# 2MBSIMMDIP.net
KiCad netlist of a schematic drawn in EAGLE
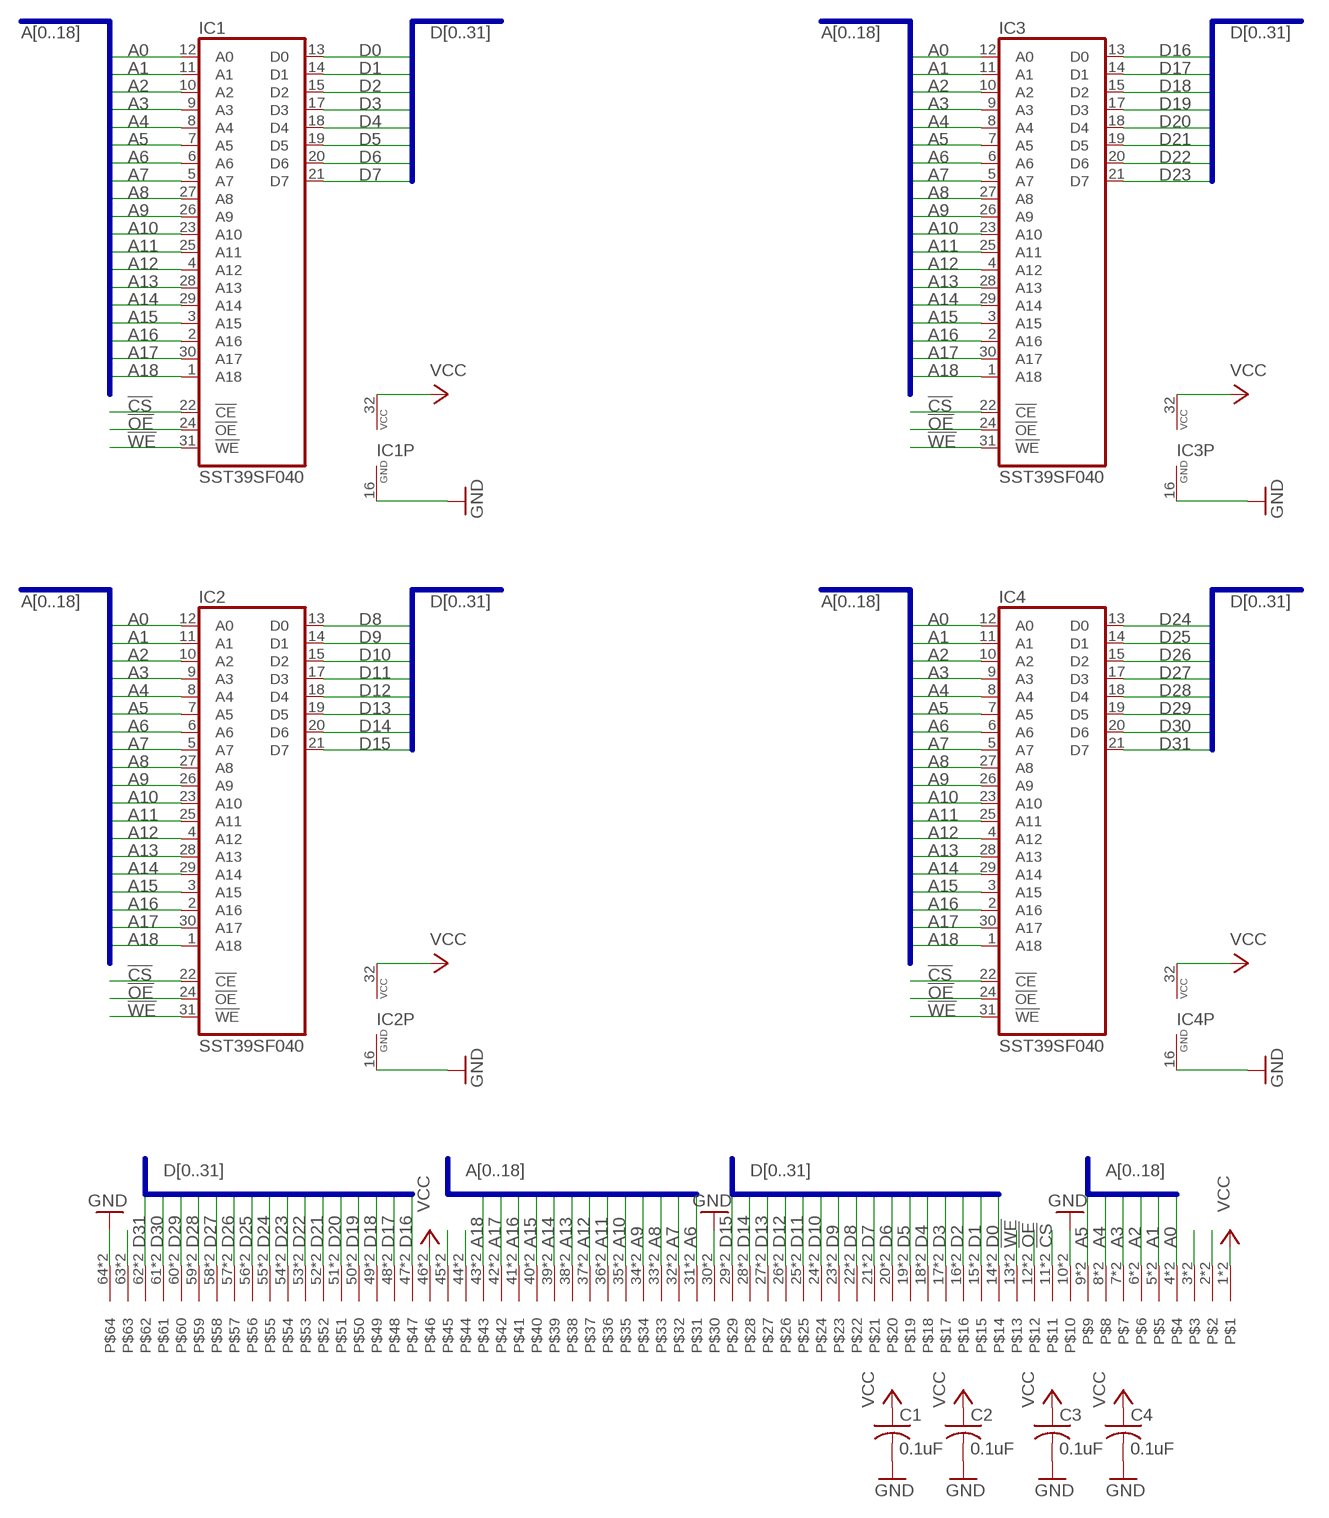
[diagram p0: schematic, sheet 1]

(export (version "E")
  (design (tool "Eeschema 10.0.6"))
  (components
    (comp (ref "C1")
      (value "0.1uF")
      (footprint "eagle-import:C1206")
      (libsource (lib "eagle-import") (part "C-USC1206"))
    )
    (comp (ref "C2")
      (value "0.1uF")
      (footprint "eagle-import:C1206")
      (libsource (lib "eagle-import") (part "C-USC1206"))
    )
    (comp (ref "C3")
      (value "0.1uF")
      (footprint "eagle-import:C1206")
      (libsource (lib "eagle-import") (part "C-USC1206"))
    )
    (comp (ref "C4")
      (value "0.1uF")
      (footprint "eagle-import:C1206")
      (libsource (lib "eagle-import") (part "C-USC1206"))
    )
    (comp (ref "CON1")
      (value "MYSIMM")
      (footprint "eagle-import:SIMM64L")
      (libsource (lib "eagle-import") (part "MYSIMM"))
    )
    (comp (ref "IC1")
      (value "SST39SF040")
      (footprint "eagle-import:DIL32-6")
      (libsource (lib "eagle-import") (part "SST39SF040"))
    )
    (comp (ref "IC2")
      (value "SST39SF040")
      (footprint "eagle-import:DIL32-6")
      (libsource (lib "eagle-import") (part "SST39SF040"))
    )
    (comp (ref "IC3")
      (value "SST39SF040")
      (footprint "eagle-import:DIL32-6")
      (libsource (lib "eagle-import") (part "SST39SF040"))
    )
    (comp (ref "IC4")
      (value "SST39SF040")
      (footprint "eagle-import:DIL32-6")
      (libsource (lib "eagle-import") (part "SST39SF040"))
    )
  )
  (nets
    (net (code "1") (name "/A0") (class "Default")
      (node (ref "CON1") (pin "4") (pinfunction "P$4_4") (pintype "bidirectional"))
      (node (ref "CON1") (pin "68") (pinfunction "P$4_68") (pintype "bidirectional"))
      (node (ref "IC1") (pin "12") (pinfunction "A0_12") (pintype "input"))
      (node (ref "IC2") (pin "12") (pinfunction "A0_12") (pintype "input"))
      (node (ref "IC3") (pin "12") (pinfunction "A0_12") (pintype "input"))
      (node (ref "IC4") (pin "12") (pinfunction "A0_12") (pintype "input"))
    )
    (net (code "2") (name "/A1") (class "Default")
      (node (ref "CON1") (pin "5") (pinfunction "P$5_5") (pintype "bidirectional"))
      (node (ref "CON1") (pin "69") (pinfunction "P$5_69") (pintype "bidirectional"))
      (node (ref "IC1") (pin "11") (pinfunction "A1_11") (pintype "input"))
      (node (ref "IC2") (pin "11") (pinfunction "A1_11") (pintype "input"))
      (node (ref "IC3") (pin "11") (pinfunction "A1_11") (pintype "input"))
      (node (ref "IC4") (pin "11") (pinfunction "A1_11") (pintype "input"))
    )
    (net (code "3") (name "/A2") (class "Default")
      (node (ref "CON1") (pin "6") (pinfunction "P$6_6") (pintype "bidirectional"))
      (node (ref "CON1") (pin "70") (pinfunction "P$6_70") (pintype "bidirectional"))
      (node (ref "IC1") (pin "10") (pinfunction "A2_10") (pintype "input"))
      (node (ref "IC2") (pin "10") (pinfunction "A2_10") (pintype "input"))
      (node (ref "IC3") (pin "10") (pinfunction "A2_10") (pintype "input"))
      (node (ref "IC4") (pin "10") (pinfunction "A2_10") (pintype "input"))
    )
    (net (code "4") (name "/A3") (class "Default")
      (node (ref "CON1") (pin "7") (pinfunction "P$7_7") (pintype "bidirectional"))
      (node (ref "CON1") (pin "71") (pinfunction "P$7_71") (pintype "bidirectional"))
      (node (ref "IC1") (pin "9") (pinfunction "A3_9") (pintype "input"))
      (node (ref "IC2") (pin "9") (pinfunction "A3_9") (pintype "input"))
      (node (ref "IC3") (pin "9") (pinfunction "A3_9") (pintype "input"))
      (node (ref "IC4") (pin "9") (pinfunction "A3_9") (pintype "input"))
    )
    (net (code "5") (name "/A4") (class "Default")
      (node (ref "CON1") (pin "72") (pinfunction "P$8_72") (pintype "bidirectional"))
      (node (ref "CON1") (pin "8") (pinfunction "P$8_8") (pintype "bidirectional"))
      (node (ref "IC1") (pin "8") (pinfunction "A4_8") (pintype "input"))
      (node (ref "IC2") (pin "8") (pinfunction "A4_8") (pintype "input"))
      (node (ref "IC3") (pin "8") (pinfunction "A4_8") (pintype "input"))
      (node (ref "IC4") (pin "8") (pinfunction "A4_8") (pintype "input"))
    )
    (net (code "6") (name "/A5") (class "Default")
      (node (ref "CON1") (pin "73") (pinfunction "P$9_73") (pintype "bidirectional"))
      (node (ref "CON1") (pin "9") (pinfunction "P$9_9") (pintype "bidirectional"))
      (node (ref "IC1") (pin "7") (pinfunction "A5_7") (pintype "input"))
      (node (ref "IC2") (pin "7") (pinfunction "A5_7") (pintype "input"))
      (node (ref "IC3") (pin "7") (pinfunction "A5_7") (pintype "input"))
      (node (ref "IC4") (pin "7") (pinfunction "A5_7") (pintype "input"))
    )
    (net (code "7") (name "/A6") (class "Default")
      (node (ref "CON1") (pin "31") (pinfunction "P$31_31") (pintype "bidirectional"))
      (node (ref "CON1") (pin "95") (pinfunction "P$31_95") (pintype "bidirectional"))
      (node (ref "IC1") (pin "6") (pinfunction "A6_6") (pintype "input"))
      (node (ref "IC2") (pin "6") (pinfunction "A6_6") (pintype "input"))
      (node (ref "IC3") (pin "6") (pinfunction "A6_6") (pintype "input"))
      (node (ref "IC4") (pin "6") (pinfunction "A6_6") (pintype "input"))
    )
    (net (code "8") (name "/A7") (class "Default")
      (node (ref "CON1") (pin "32") (pinfunction "P$32_32") (pintype "bidirectional"))
      (node (ref "CON1") (pin "96") (pinfunction "P$32_96") (pintype "bidirectional"))
      (node (ref "IC1") (pin "5") (pinfunction "A7_5") (pintype "input"))
      (node (ref "IC2") (pin "5") (pinfunction "A7_5") (pintype "input"))
      (node (ref "IC3") (pin "5") (pinfunction "A7_5") (pintype "input"))
      (node (ref "IC4") (pin "5") (pinfunction "A7_5") (pintype "input"))
    )
    (net (code "9") (name "/A8") (class "Default")
      (node (ref "CON1") (pin "33") (pinfunction "P$33_33") (pintype "bidirectional"))
      (node (ref "CON1") (pin "97") (pinfunction "P$33_97") (pintype "bidirectional"))
      (node (ref "IC1") (pin "27") (pinfunction "A8_27") (pintype "input"))
      (node (ref "IC2") (pin "27") (pinfunction "A8_27") (pintype "input"))
      (node (ref "IC3") (pin "27") (pinfunction "A8_27") (pintype "input"))
      (node (ref "IC4") (pin "27") (pinfunction "A8_27") (pintype "input"))
    )
    (net (code "10") (name "/A9") (class "Default")
      (node (ref "CON1") (pin "34") (pinfunction "P$34_34") (pintype "bidirectional"))
      (node (ref "CON1") (pin "98") (pinfunction "P$34_98") (pintype "bidirectional"))
      (node (ref "IC1") (pin "26") (pinfunction "A9_26") (pintype "input"))
      (node (ref "IC2") (pin "26") (pinfunction "A9_26") (pintype "input"))
      (node (ref "IC3") (pin "26") (pinfunction "A9_26") (pintype "input"))
      (node (ref "IC4") (pin "26") (pinfunction "A9_26") (pintype "input"))
    )
    (net (code "11") (name "/A10") (class "Default")
      (node (ref "CON1") (pin "35") (pinfunction "P$35_35") (pintype "bidirectional"))
      (node (ref "CON1") (pin "99") (pinfunction "P$35_99") (pintype "bidirectional"))
      (node (ref "IC1") (pin "23") (pinfunction "A10_23") (pintype "input"))
      (node (ref "IC2") (pin "23") (pinfunction "A10_23") (pintype "input"))
      (node (ref "IC3") (pin "23") (pinfunction "A10_23") (pintype "input"))
      (node (ref "IC4") (pin "23") (pinfunction "A10_23") (pintype "input"))
    )
    (net (code "12") (name "/A11") (class "Default")
      (node (ref "CON1") (pin "100") (pinfunction "P$36_100") (pintype "bidirectional"))
      (node (ref "CON1") (pin "36") (pinfunction "P$36_36") (pintype "bidirectional"))
      (node (ref "IC1") (pin "25") (pinfunction "A11_25") (pintype "input"))
      (node (ref "IC2") (pin "25") (pinfunction "A11_25") (pintype "input"))
      (node (ref "IC3") (pin "25") (pinfunction "A11_25") (pintype "input"))
      (node (ref "IC4") (pin "25") (pinfunction "A11_25") (pintype "input"))
    )
    (net (code "13") (name "/A12") (class "Default")
      (node (ref "CON1") (pin "101") (pinfunction "P$37_101") (pintype "bidirectional"))
      (node (ref "CON1") (pin "37") (pinfunction "P$37_37") (pintype "bidirectional"))
      (node (ref "IC1") (pin "4") (pinfunction "A12_4") (pintype "input"))
      (node (ref "IC2") (pin "4") (pinfunction "A12_4") (pintype "input"))
      (node (ref "IC3") (pin "4") (pinfunction "A12_4") (pintype "input"))
      (node (ref "IC4") (pin "4") (pinfunction "A12_4") (pintype "input"))
    )
    (net (code "14") (name "/A13") (class "Default")
      (node (ref "CON1") (pin "102") (pinfunction "P$38_102") (pintype "bidirectional"))
      (node (ref "CON1") (pin "38") (pinfunction "P$38_38") (pintype "bidirectional"))
      (node (ref "IC1") (pin "28") (pinfunction "A13_28") (pintype "input"))
      (node (ref "IC2") (pin "28") (pinfunction "A13_28") (pintype "input"))
      (node (ref "IC3") (pin "28") (pinfunction "A13_28") (pintype "input"))
      (node (ref "IC4") (pin "28") (pinfunction "A13_28") (pintype "input"))
    )
    (net (code "15") (name "/A14") (class "Default")
      (node (ref "CON1") (pin "103") (pinfunction "P$39_103") (pintype "bidirectional"))
      (node (ref "CON1") (pin "39") (pinfunction "P$39_39") (pintype "bidirectional"))
      (node (ref "IC1") (pin "29") (pinfunction "A14_29") (pintype "input"))
      (node (ref "IC2") (pin "29") (pinfunction "A14_29") (pintype "input"))
      (node (ref "IC3") (pin "29") (pinfunction "A14_29") (pintype "input"))
      (node (ref "IC4") (pin "29") (pinfunction "A14_29") (pintype "input"))
    )
    (net (code "16") (name "/A15") (class "Default")
      (node (ref "CON1") (pin "104") (pinfunction "P$40_104") (pintype "bidirectional"))
      (node (ref "CON1") (pin "40") (pinfunction "P$40_40") (pintype "bidirectional"))
      (node (ref "IC1") (pin "3") (pinfunction "A15_3") (pintype "input"))
      (node (ref "IC2") (pin "3") (pinfunction "A15_3") (pintype "input"))
      (node (ref "IC3") (pin "3") (pinfunction "A15_3") (pintype "input"))
      (node (ref "IC4") (pin "3") (pinfunction "A15_3") (pintype "input"))
    )
    (net (code "17") (name "/A16") (class "Default")
      (node (ref "CON1") (pin "105") (pinfunction "P$41_105") (pintype "bidirectional"))
      (node (ref "CON1") (pin "41") (pinfunction "P$41_41") (pintype "bidirectional"))
      (node (ref "IC1") (pin "2") (pinfunction "A16_2") (pintype "input"))
      (node (ref "IC2") (pin "2") (pinfunction "A16_2") (pintype "input"))
      (node (ref "IC3") (pin "2") (pinfunction "A16_2") (pintype "input"))
      (node (ref "IC4") (pin "2") (pinfunction "A16_2") (pintype "input"))
    )
    (net (code "18") (name "/A17") (class "Default")
      (node (ref "CON1") (pin "106") (pinfunction "P$42_106") (pintype "bidirectional"))
      (node (ref "CON1") (pin "42") (pinfunction "P$42_42") (pintype "bidirectional"))
      (node (ref "IC1") (pin "30") (pinfunction "A17_30") (pintype "input"))
      (node (ref "IC2") (pin "30") (pinfunction "A17_30") (pintype "input"))
      (node (ref "IC3") (pin "30") (pinfunction "A17_30") (pintype "input"))
      (node (ref "IC4") (pin "30") (pinfunction "A17_30") (pintype "input"))
    )
    (net (code "19") (name "/A18") (class "Default")
      (node (ref "CON1") (pin "107") (pinfunction "P$43_107") (pintype "bidirectional"))
      (node (ref "CON1") (pin "43") (pinfunction "P$43_43") (pintype "bidirectional"))
      (node (ref "IC1") (pin "1") (pinfunction "A18_1") (pintype "input"))
      (node (ref "IC2") (pin "1") (pinfunction "A18_1") (pintype "input"))
      (node (ref "IC3") (pin "1") (pinfunction "A18_1") (pintype "input"))
      (node (ref "IC4") (pin "1") (pinfunction "A18_1") (pintype "input"))
    )
    (net (code "21") (name "/D0") (class "Default")
      (node (ref "CON1") (pin "14") (pinfunction "P$14_14") (pintype "bidirectional"))
      (node (ref "CON1") (pin "78") (pinfunction "P$14_78") (pintype "bidirectional"))
      (node (ref "IC1") (pin "13") (pinfunction "D0_13") (pintype "tri_state"))
    )
    (net (code "22") (name "/D1") (class "Default")
      (node (ref "CON1") (pin "15") (pinfunction "P$15_15") (pintype "bidirectional"))
      (node (ref "CON1") (pin "79") (pinfunction "P$15_79") (pintype "bidirectional"))
      (node (ref "IC1") (pin "14") (pinfunction "D1_14") (pintype "tri_state"))
    )
    (net (code "23") (name "/D2") (class "Default")
      (node (ref "CON1") (pin "16") (pinfunction "P$16_16") (pintype "bidirectional"))
      (node (ref "CON1") (pin "80") (pinfunction "P$16_80") (pintype "bidirectional"))
      (node (ref "IC1") (pin "15") (pinfunction "D2_15") (pintype "tri_state"))
    )
    (net (code "24") (name "/D3") (class "Default")
      (node (ref "CON1") (pin "17") (pinfunction "P$17_17") (pintype "bidirectional"))
      (node (ref "CON1") (pin "81") (pinfunction "P$17_81") (pintype "bidirectional"))
      (node (ref "IC1") (pin "17") (pinfunction "D3_17") (pintype "tri_state"))
    )
    (net (code "25") (name "/D4") (class "Default")
      (node (ref "CON1") (pin "18") (pinfunction "P$18_18") (pintype "bidirectional"))
      (node (ref "CON1") (pin "82") (pinfunction "P$18_82") (pintype "bidirectional"))
      (node (ref "IC1") (pin "18") (pinfunction "D4_18") (pintype "tri_state"))
    )
    (net (code "26") (name "/D5") (class "Default")
      (node (ref "CON1") (pin "19") (pinfunction "P$19_19") (pintype "bidirectional"))
      (node (ref "CON1") (pin "83") (pinfunction "P$19_83") (pintype "bidirectional"))
      (node (ref "IC1") (pin "19") (pinfunction "D5_19") (pintype "tri_state"))
    )
    (net (code "27") (name "/D6") (class "Default")
      (node (ref "CON1") (pin "20") (pinfunction "P$20_20") (pintype "bidirectional"))
      (node (ref "CON1") (pin "84") (pinfunction "P$20_84") (pintype "bidirectional"))
      (node (ref "IC1") (pin "20") (pinfunction "D6_20") (pintype "tri_state"))
    )
    (net (code "28") (name "/D7") (class "Default")
      (node (ref "CON1") (pin "21") (pinfunction "P$21_21") (pintype "bidirectional"))
      (node (ref "CON1") (pin "85") (pinfunction "P$21_85") (pintype "bidirectional"))
      (node (ref "IC1") (pin "21") (pinfunction "D7_21") (pintype "tri_state"))
    )
    (net (code "29") (name "/D8") (class "Default")
      (node (ref "CON1") (pin "22") (pinfunction "P$22_22") (pintype "bidirectional"))
      (node (ref "CON1") (pin "86") (pinfunction "P$22_86") (pintype "bidirectional"))
      (node (ref "IC2") (pin "13") (pinfunction "D0_13") (pintype "tri_state"))
    )
    (net (code "30") (name "/D9") (class "Default")
      (node (ref "CON1") (pin "23") (pinfunction "P$23_23") (pintype "bidirectional"))
      (node (ref "CON1") (pin "87") (pinfunction "P$23_87") (pintype "bidirectional"))
      (node (ref "IC2") (pin "14") (pinfunction "D1_14") (pintype "tri_state"))
    )
    (net (code "31") (name "/D10") (class "Default")
      (node (ref "CON1") (pin "24") (pinfunction "P$24_24") (pintype "bidirectional"))
      (node (ref "CON1") (pin "88") (pinfunction "P$24_88") (pintype "bidirectional"))
      (node (ref "IC2") (pin "15") (pinfunction "D2_15") (pintype "tri_state"))
    )
    (net (code "32") (name "/D11") (class "Default")
      (node (ref "CON1") (pin "25") (pinfunction "P$25_25") (pintype "bidirectional"))
      (node (ref "CON1") (pin "89") (pinfunction "P$25_89") (pintype "bidirectional"))
      (node (ref "IC2") (pin "17") (pinfunction "D3_17") (pintype "tri_state"))
    )
    (net (code "33") (name "/D12") (class "Default")
      (node (ref "CON1") (pin "26") (pinfunction "P$26_26") (pintype "bidirectional"))
      (node (ref "CON1") (pin "90") (pinfunction "P$26_90") (pintype "bidirectional"))
      (node (ref "IC2") (pin "18") (pinfunction "D4_18") (pintype "tri_state"))
    )
    (net (code "34") (name "/D13") (class "Default")
      (node (ref "CON1") (pin "27") (pinfunction "P$27_27") (pintype "bidirectional"))
      (node (ref "CON1") (pin "91") (pinfunction "P$27_91") (pintype "bidirectional"))
      (node (ref "IC2") (pin "19") (pinfunction "D5_19") (pintype "tri_state"))
    )
    (net (code "35") (name "/D14") (class "Default")
      (node (ref "CON1") (pin "28") (pinfunction "P$28_28") (pintype "bidirectional"))
      (node (ref "CON1") (pin "92") (pinfunction "P$28_92") (pintype "bidirectional"))
      (node (ref "IC2") (pin "20") (pinfunction "D6_20") (pintype "tri_state"))
    )
    (net (code "36") (name "/D15") (class "Default")
      (node (ref "CON1") (pin "29") (pinfunction "P$29_29") (pintype "bidirectional"))
      (node (ref "CON1") (pin "93") (pinfunction "P$29_93") (pintype "bidirectional"))
      (node (ref "IC2") (pin "21") (pinfunction "D7_21") (pintype "tri_state"))
    )
    (net (code "37") (name "/D16") (class "Default")
      (node (ref "CON1") (pin "111") (pinfunction "P$47_111") (pintype "bidirectional"))
      (node (ref "CON1") (pin "47") (pinfunction "P$47_47") (pintype "bidirectional"))
      (node (ref "IC3") (pin "13") (pinfunction "D0_13") (pintype "tri_state"))
    )
    (net (code "38") (name "/D17") (class "Default")
      (node (ref "CON1") (pin "112") (pinfunction "P$48_112") (pintype "bidirectional"))
      (node (ref "CON1") (pin "48") (pinfunction "P$48_48") (pintype "bidirectional"))
      (node (ref "IC3") (pin "14") (pinfunction "D1_14") (pintype "tri_state"))
    )
    (net (code "39") (name "/D18") (class "Default")
      (node (ref "CON1") (pin "113") (pinfunction "P$49_113") (pintype "bidirectional"))
      (node (ref "CON1") (pin "49") (pinfunction "P$49_49") (pintype "bidirectional"))
      (node (ref "IC3") (pin "15") (pinfunction "D2_15") (pintype "tri_state"))
    )
    (net (code "40") (name "/D19") (class "Default")
      (node (ref "CON1") (pin "114") (pinfunction "P$50_114") (pintype "bidirectional"))
      (node (ref "CON1") (pin "50") (pinfunction "P$50_50") (pintype "bidirectional"))
      (node (ref "IC3") (pin "17") (pinfunction "D3_17") (pintype "tri_state"))
    )
    (net (code "41") (name "/D20") (class "Default")
      (node (ref "CON1") (pin "115") (pinfunction "P$51_115") (pintype "bidirectional"))
      (node (ref "CON1") (pin "51") (pinfunction "P$51_51") (pintype "bidirectional"))
      (node (ref "IC3") (pin "18") (pinfunction "D4_18") (pintype "tri_state"))
    )
    (net (code "42") (name "/D21") (class "Default")
      (node (ref "CON1") (pin "116") (pinfunction "P$52_116") (pintype "bidirectional"))
      (node (ref "CON1") (pin "52") (pinfunction "P$52_52") (pintype "bidirectional"))
      (node (ref "IC3") (pin "19") (pinfunction "D5_19") (pintype "tri_state"))
    )
    (net (code "43") (name "/D22") (class "Default")
      (node (ref "CON1") (pin "117") (pinfunction "P$53_117") (pintype "bidirectional"))
      (node (ref "CON1") (pin "53") (pinfunction "P$53_53") (pintype "bidirectional"))
      (node (ref "IC3") (pin "20") (pinfunction "D6_20") (pintype "tri_state"))
    )
    (net (code "44") (name "/D23") (class "Default")
      (node (ref "CON1") (pin "118") (pinfunction "P$54_118") (pintype "bidirectional"))
      (node (ref "CON1") (pin "54") (pinfunction "P$54_54") (pintype "bidirectional"))
      (node (ref "IC3") (pin "21") (pinfunction "D7_21") (pintype "tri_state"))
    )
    (net (code "45") (name "/D24") (class "Default")
      (node (ref "CON1") (pin "119") (pinfunction "P$55_119") (pintype "bidirectional"))
      (node (ref "CON1") (pin "55") (pinfunction "P$55_55") (pintype "bidirectional"))
      (node (ref "IC4") (pin "13") (pinfunction "D0_13") (pintype "tri_state"))
    )
    (net (code "46") (name "/D25") (class "Default")
      (node (ref "CON1") (pin "120") (pinfunction "P$56_120") (pintype "bidirectional"))
      (node (ref "CON1") (pin "56") (pinfunction "P$56_56") (pintype "bidirectional"))
      (node (ref "IC4") (pin "14") (pinfunction "D1_14") (pintype "tri_state"))
    )
    (net (code "47") (name "/D26") (class "Default")
      (node (ref "CON1") (pin "121") (pinfunction "P$57_121") (pintype "bidirectional"))
      (node (ref "CON1") (pin "57") (pinfunction "P$57_57") (pintype "bidirectional"))
      (node (ref "IC4") (pin "15") (pinfunction "D2_15") (pintype "tri_state"))
    )
    (net (code "48") (name "/D27") (class "Default")
      (node (ref "CON1") (pin "122") (pinfunction "P$58_122") (pintype "bidirectional"))
      (node (ref "CON1") (pin "58") (pinfunction "P$58_58") (pintype "bidirectional"))
      (node (ref "IC4") (pin "17") (pinfunction "D3_17") (pintype "tri_state"))
    )
    (net (code "49") (name "/D28") (class "Default")
      (node (ref "CON1") (pin "123") (pinfunction "P$59_123") (pintype "bidirectional"))
      (node (ref "CON1") (pin "59") (pinfunction "P$59_59") (pintype "bidirectional"))
      (node (ref "IC4") (pin "18") (pinfunction "D4_18") (pintype "tri_state"))
    )
    (net (code "50") (name "/D29") (class "Default")
      (node (ref "CON1") (pin "124") (pinfunction "P$60_124") (pintype "bidirectional"))
      (node (ref "CON1") (pin "60") (pinfunction "P$60_60") (pintype "bidirectional"))
      (node (ref "IC4") (pin "19") (pinfunction "D5_19") (pintype "tri_state"))
    )
    (net (code "51") (name "/D30") (class "Default")
      (node (ref "CON1") (pin "125") (pinfunction "P$61_125") (pintype "bidirectional"))
      (node (ref "CON1") (pin "61") (pinfunction "P$61_61") (pintype "bidirectional"))
      (node (ref "IC4") (pin "20") (pinfunction "D6_20") (pintype "tri_state"))
    )
    (net (code "52") (name "/D31") (class "Default")
      (node (ref "CON1") (pin "126") (pinfunction "P$62_126") (pintype "bidirectional"))
      (node (ref "CON1") (pin "62") (pinfunction "P$62_62") (pintype "bidirectional"))
      (node (ref "IC4") (pin "21") (pinfunction "D7_21") (pintype "tri_state"))
    )
    (net (code "54") (name "/~{CS}") (class "Default")
      (node (ref "CON1") (pin "11") (pinfunction "P$11_11") (pintype "bidirectional"))
      (node (ref "CON1") (pin "75") (pinfunction "P$11_75") (pintype "bidirectional"))
      (node (ref "IC1") (pin "22") (pinfunction "~{CE}_22") (pintype "input"))
      (node (ref "IC2") (pin "22") (pinfunction "~{CE}_22") (pintype "input"))
      (node (ref "IC3") (pin "22") (pinfunction "~{CE}_22") (pintype "input"))
      (node (ref "IC4") (pin "22") (pinfunction "~{CE}_22") (pintype "input"))
    )
    (net (code "55") (name "/~{OE}") (class "Default")
      (node (ref "CON1") (pin "12") (pinfunction "P$12_12") (pintype "bidirectional"))
      (node (ref "CON1") (pin "76") (pinfunction "P$12_76") (pintype "bidirectional"))
      (node (ref "IC1") (pin "24") (pinfunction "~{OE}_24") (pintype "input"))
      (node (ref "IC2") (pin "24") (pinfunction "~{OE}_24") (pintype "input"))
      (node (ref "IC3") (pin "24") (pinfunction "~{OE}_24") (pintype "input"))
      (node (ref "IC4") (pin "24") (pinfunction "~{OE}_24") (pintype "input"))
    )
    (net (code "56") (name "/~{WE}") (class "Default")
      (node (ref "CON1") (pin "13") (pinfunction "P$13_13") (pintype "bidirectional"))
      (node (ref "CON1") (pin "77") (pinfunction "P$13_77") (pintype "bidirectional"))
      (node (ref "IC1") (pin "31") (pinfunction "~{WE}_31") (pintype "input"))
      (node (ref "IC2") (pin "31") (pinfunction "~{WE}_31") (pintype "input"))
      (node (ref "IC3") (pin "31") (pinfunction "~{WE}_31") (pintype "input"))
      (node (ref "IC4") (pin "31") (pinfunction "~{WE}_31") (pintype "input"))
    )
    (net (code "57") (name "GND") (class "Default")
      (node (ref "C1") (pin "2") (pinfunction "2_2") (pintype "passive"))
      (node (ref "C2") (pin "2") (pinfunction "2_2") (pintype "passive"))
      (node (ref "C3") (pin "2") (pinfunction "2_2") (pintype "passive"))
      (node (ref "C4") (pin "2") (pinfunction "2_2") (pintype "passive"))
      (node (ref "CON1") (pin "10") (pinfunction "P$10_10") (pintype "bidirectional"))
      (node (ref "CON1") (pin "128") (pinfunction "P$64_128") (pintype "bidirectional"))
      (node (ref "CON1") (pin "30") (pinfunction "P$30_30") (pintype "bidirectional"))
      (node (ref "CON1") (pin "64") (pinfunction "P$64_64") (pintype "bidirectional"))
      (node (ref "CON1") (pin "74") (pinfunction "P$10_74") (pintype "bidirectional"))
      (node (ref "CON1") (pin "94") (pinfunction "P$30_94") (pintype "bidirectional"))
      (node (ref "IC1") (pin "16") (pinfunction "GND_16") (pintype "power_in"))
      (node (ref "IC2") (pin "16") (pinfunction "GND_16") (pintype "power_in"))
      (node (ref "IC3") (pin "16") (pinfunction "GND_16") (pintype "power_in"))
      (node (ref "IC4") (pin "16") (pinfunction "GND_16") (pintype "power_in"))
    )
    (net (code "58") (name "Net-(CON1-P$2-Pad2)") (class "Default")
      (node (ref "CON1") (pin "2") (pinfunction "P$2_2") (pintype "bidirectional"))
      (node (ref "CON1") (pin "66") (pinfunction "P$2_66") (pintype "bidirectional"))
    )
    (net (code "59") (name "Net-(CON1-P$3-Pad3)") (class "Default")
      (node (ref "CON1") (pin "3") (pinfunction "P$3_3") (pintype "bidirectional"))
      (node (ref "CON1") (pin "67") (pinfunction "P$3_67") (pintype "bidirectional"))
    )
    (net (code "60") (name "Net-(CON1-P$44-Pad108)") (class "Default")
      (node (ref "CON1") (pin "108") (pinfunction "P$44_108") (pintype "bidirectional"))
      (node (ref "CON1") (pin "44") (pinfunction "P$44_44") (pintype "bidirectional"))
    )
    (net (code "61") (name "Net-(CON1-P$45-Pad109)") (class "Default")
      (node (ref "CON1") (pin "109") (pinfunction "P$45_109") (pintype "bidirectional"))
      (node (ref "CON1") (pin "45") (pinfunction "P$45_45") (pintype "bidirectional"))
    )
    (net (code "62") (name "Net-(CON1-P$63-Pad127)") (class "Default")
      (node (ref "CON1") (pin "127") (pinfunction "P$63_127") (pintype "bidirectional"))
      (node (ref "CON1") (pin "63") (pinfunction "P$63_63") (pintype "bidirectional"))
    )
    (net (code "63") (name "VCC") (class "Default")
      (node (ref "C1") (pin "1") (pinfunction "1_1") (pintype "passive"))
      (node (ref "C2") (pin "1") (pinfunction "1_1") (pintype "passive"))
      (node (ref "C3") (pin "1") (pinfunction "1_1") (pintype "passive"))
      (node (ref "C4") (pin "1") (pinfunction "1_1") (pintype "passive"))
      (node (ref "CON1") (pin "1") (pinfunction "P$1_1") (pintype "bidirectional"))
      (node (ref "CON1") (pin "110") (pinfunction "P$46_110") (pintype "bidirectional"))
      (node (ref "CON1") (pin "46") (pinfunction "P$46_46") (pintype "bidirectional"))
      (node (ref "CON1") (pin "65") (pinfunction "P$1_65") (pintype "bidirectional"))
      (node (ref "IC1") (pin "32") (pinfunction "VCC_32") (pintype "power_in"))
      (node (ref "IC2") (pin "32") (pinfunction "VCC_32") (pintype "power_in"))
      (node (ref "IC3") (pin "32") (pinfunction "VCC_32") (pintype "power_in"))
      (node (ref "IC4") (pin "32") (pinfunction "VCC_32") (pintype "power_in"))
    )
  )
)
